# USB.net
KiCad netlist of a schematic drawn in Altium Designer
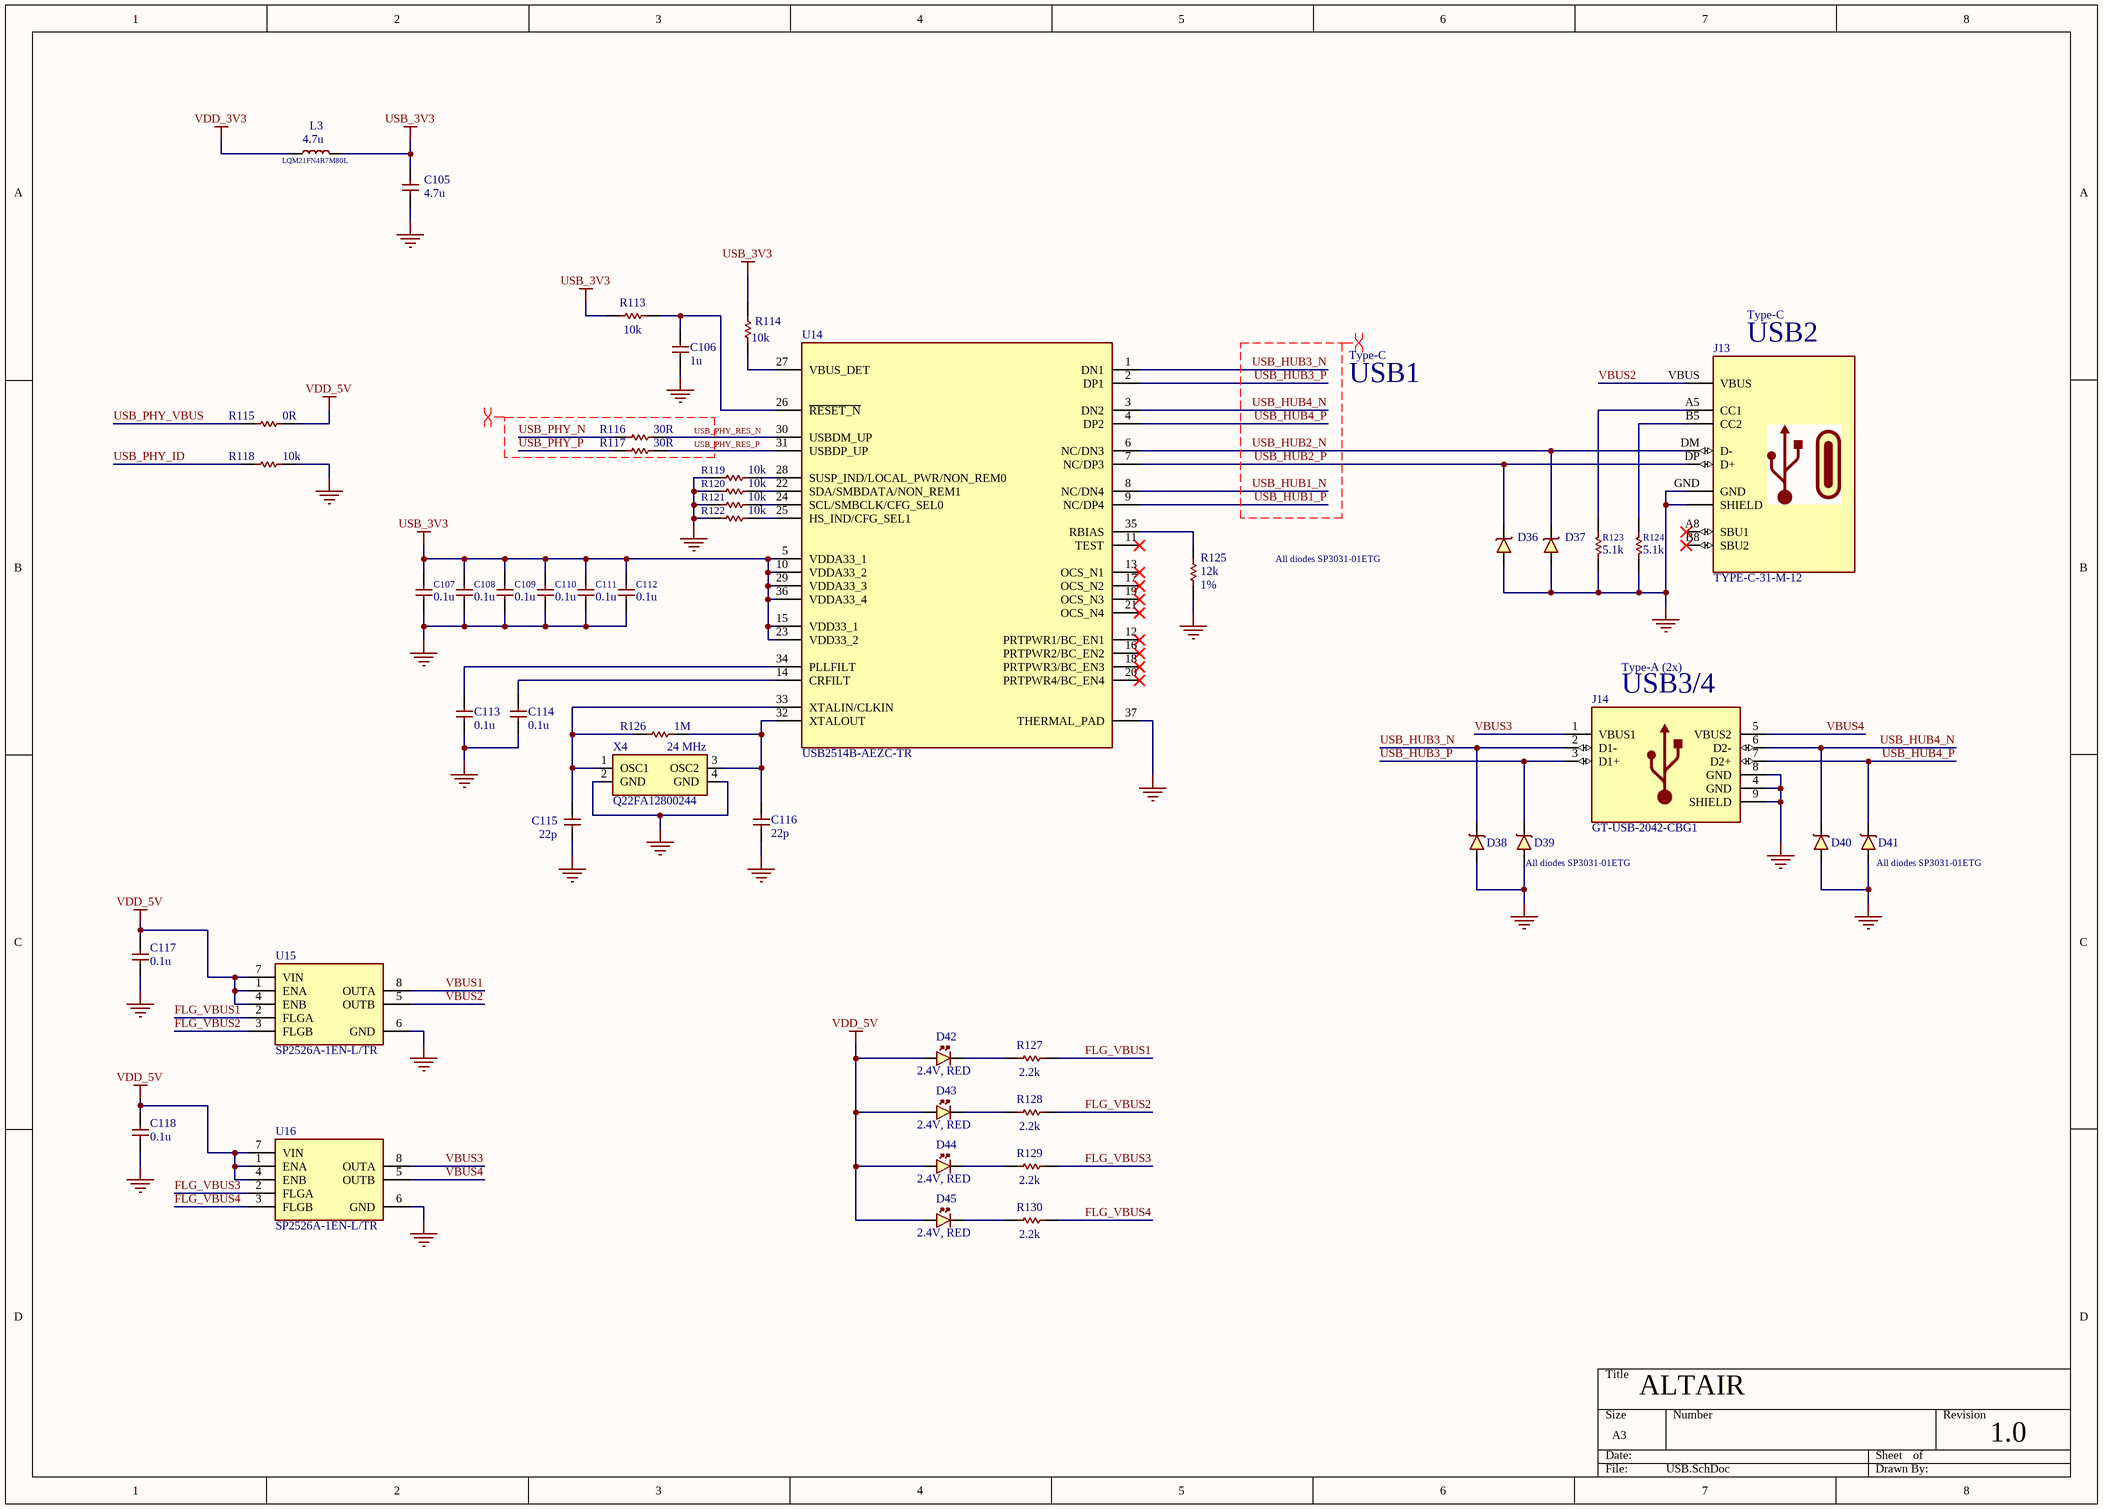
[diagram p0: USB.SchDoc]

(export (version "E")
  (design (tool "Eeschema 10.0.6"))
  (components
    (comp (ref "C105")
      (value "4.7u")
      (footprint "CAP_0402")
      (description "Capacitor SMD 0402")
      (fields (field (name "PART NO") "HGC0402R5475M250NTEJ") (field (name "JLCPCB PART #") "C22367824"))
      (libsource (lib "personalGenericLib") (part "CAP_0402"))
    )
    (comp (ref "C106")
      (value "1u")
      (footprint "CAP_0402")
      (description "Capacitor SMD 0402")
      (fields (field (name "JLCPCB PART #") "C14445") (field (name "PART NO") "CL05A105KP5NNNC"))
      (libsource (lib "personalGenericLib") (part "CAP_0402"))
    )
    (comp (ref "C107")
      (value "0.1u")
      (footprint "CAP_0402")
      (description "Capacitor SMD 0402")
      (fields (field (name "PART NO") "CL05B104KO5NNNC") (field (name "JLCPCB PART #") "C338112"))
      (libsource (lib "personalGenericLib") (part "CAP_0402"))
    )
    (comp (ref "C108")
      (value "0.1u")
      (footprint "CAP_0402")
      (description "Capacitor SMD 0402")
      (fields (field (name "PART NO") "CL05B104KO5NNNC") (field (name "JLCPCB PART #") "C338112"))
      (libsource (lib "personalGenericLib") (part "CAP_0402"))
    )
    (comp (ref "C109")
      (value "0.1u")
      (footprint "CAP_0402")
      (description "Capacitor SMD 0402")
      (fields (field (name "PART NO") "CL05B104KO5NNNC") (field (name "JLCPCB PART #") "C338112"))
      (libsource (lib "personalGenericLib") (part "CAP_0402"))
    )
    (comp (ref "C110")
      (value "0.1u")
      (footprint "CAP_0402")
      (description "Capacitor SMD 0402")
      (fields (field (name "PART NO") "CL05B104KO5NNNC") (field (name "JLCPCB PART #") "C338112"))
      (libsource (lib "personalGenericLib") (part "CAP_0402"))
    )
    (comp (ref "C111")
      (value "0.1u")
      (footprint "CAP_0402")
      (description "Capacitor SMD 0402")
      (fields (field (name "PART NO") "CL05B104KO5NNNC") (field (name "JLCPCB PART #") "C338112"))
      (libsource (lib "personalGenericLib") (part "CAP_0402"))
    )
    (comp (ref "C112")
      (value "0.1u")
      (footprint "CAP_0402")
      (description "Capacitor SMD 0402")
      (fields (field (name "PART NO") "CL05B104KO5NNNC") (field (name "JLCPCB PART #") "C338112"))
      (libsource (lib "personalGenericLib") (part "CAP_0402"))
    )
    (comp (ref "C113")
      (value "0.1u")
      (footprint "CAP_0402")
      (description "Capacitor SMD 0402")
      (fields (field (name "PART NO") "CL05B104KO5NNNC") (field (name "JLCPCB PART #") "C338112"))
      (libsource (lib "personalGenericLib") (part "CAP_0402"))
    )
    (comp (ref "C114")
      (value "0.1u")
      (footprint "CAP_0402")
      (description "Capacitor SMD 0402")
      (fields (field (name "PART NO") "CL05B104KO5NNNC") (field (name "JLCPCB PART #") "C338112"))
      (libsource (lib "personalGenericLib") (part "CAP_0402"))
    )
    (comp (ref "C115")
      (value "22p")
      (footprint "CAP_0402")
      (description "Capacitor SMD 0402")
      (fields (field (name "PART NO") "CC0402JRNPO8BN220") (field (name "JLCPCB PART #") "C541361"))
      (libsource (lib "personalGenericLib") (part "CAP_0402"))
    )
    (comp (ref "C116")
      (value "22p")
      (footprint "CAP_0402")
      (description "Capacitor SMD 0402")
      (fields (field (name "PART NO") "CC0402JRNPO8BN220") (field (name "JLCPCB PART #") "C541361"))
      (libsource (lib "personalGenericLib") (part "CAP_0402"))
    )
    (comp (ref "C117")
      (value "0.1u")
      (footprint "CAP_0402")
      (description "Capacitor SMD 0402")
      (fields (field (name "PART NO") "CL05B104KO5NNNC") (field (name "JLCPCB PART #") "C338112"))
      (libsource (lib "personalGenericLib") (part "CAP_0402"))
    )
    (comp (ref "C118")
      (value "0.1u")
      (footprint "CAP_0402")
      (description "Capacitor SMD 0402")
      (fields (field (name "PART NO") "CL05B104KO5NNNC") (field (name "JLCPCB PART #") "C338112"))
      (libsource (lib "personalGenericLib") (part "CAP_0402"))
    )
    (comp (ref "D36")
      (value "SP3031-01ETG")
      (footprint "SP303101ETG")
      (description "TVS Diode (Uni-directional)")
      (fields (field (name "JLCPCB PART #") "C207283"))
      (libsource (lib "personalGenericLib") (part "SP3031-01ETG"))
    )
    (comp (ref "D37")
      (value "SP3031-01ETG")
      (footprint "SP303101ETG")
      (description "TVS Diode (Uni-directional)")
      (fields (field (name "JLCPCB PART #") "C207283"))
      (libsource (lib "personalGenericLib") (part "SP3031-01ETG"))
    )
    (comp (ref "D38")
      (value "SP3031-01ETG")
      (footprint "SP303101ETG")
      (description "TVS Diode (Uni-directional)")
      (fields (field (name "JLCPCB PART #") "C207283"))
      (libsource (lib "personalGenericLib") (part "SP3031-01ETG"))
    )
    (comp (ref "D39")
      (value "SP3031-01ETG")
      (footprint "SP303101ETG")
      (description "TVS Diode (Uni-directional)")
      (fields (field (name "JLCPCB PART #") "C207283"))
      (libsource (lib "personalGenericLib") (part "SP3031-01ETG"))
    )
    (comp (ref "D40")
      (value "SP3031-01ETG")
      (footprint "SP303101ETG")
      (description "TVS Diode (Uni-directional)")
      (fields (field (name "JLCPCB PART #") "C207283"))
      (libsource (lib "personalGenericLib") (part "SP3031-01ETG"))
    )
    (comp (ref "D41")
      (value "SP3031-01ETG")
      (footprint "SP303101ETG")
      (description "TVS Diode (Uni-directional)")
      (fields (field (name "JLCPCB PART #") "C207283"))
      (libsource (lib "personalGenericLib") (part "SP3031-01ETG"))
    )
    (comp (ref "D42")
      (value "RED")
      (footprint "LED_0805_RED")
      (description "LED 0805 RED SMD")
      (fields
        (field (name "JLCPCB PART #") "C497952")
        (field (name "NOTE/MISC") "2.4V, RED")
        (field (name "PART NO") "HL-PSC-2012S9AC")
      )
      (libsource (lib "personalGenericLib") (part "LED_0805_RED"))
    )
    (comp (ref "D43")
      (value "RED")
      (footprint "LED_0805_RED")
      (description "LED 0805 RED SMD")
      (fields
        (field (name "JLCPCB PART #") "C497952")
        (field (name "NOTE/MISC") "2.4V, RED")
        (field (name "PART NO") "HL-PSC-2012S9AC")
      )
      (libsource (lib "personalGenericLib") (part "LED_0805_RED"))
    )
    (comp (ref "D44")
      (value "RED")
      (footprint "LED_0805_RED")
      (description "LED 0805 RED SMD")
      (fields
        (field (name "JLCPCB PART #") "C497952")
        (field (name "NOTE/MISC") "2.4V, RED")
        (field (name "PART NO") "HL-PSC-2012S9AC")
      )
      (libsource (lib "personalGenericLib") (part "LED_0805_RED"))
    )
    (comp (ref "D45")
      (value "RED")
      (footprint "LED_0805_RED")
      (description "LED 0805 RED SMD")
      (fields
        (field (name "JLCPCB PART #") "C497952")
        (field (name "NOTE/MISC") "2.4V, RED")
        (field (name "PART NO") "HL-PSC-2012S9AC")
      )
      (libsource (lib "personalGenericLib") (part "LED_0805_RED"))
    )
    (comp (ref "J13")
      (value "TYPE-C-31-M-12")
      (footprint "HRO_TYPE-C-31-M-12")
      (description "USB2.0, Type C, Top mount, CH 1.68mm, Dual Row SMT")
      (fields (field (name "JLCPCB PART #") "C165948"))
      (libsource (lib "personalGenericLib") (part "TYPE-C-31-M-12"))
    )
    (comp (ref "J14")
      (value "GT-USB-2042-CBG1")
      (footprint "GT-USB-2042-CBG1")
      (description "2x USB Type-A Female Connector")
      (fields (field (name "JLCPCB PART #") "C2911522"))
      (libsource (lib "personalGenericLib") (part "GT-USB-2042-CBG1"))
    )
    (comp (ref "L3")
      (value "4.7u")
      (footprint "INDC2012X145N")
      (description "Inductor")
      (fields
        (field (name "NOTE/MISC") "LQM21FN4R7M80L")
        (field (name "PART NO") "LQM21FN4R7M80L")
        (field (name "JLCPCB PART #") "C464406")
      )
      (libsource (lib "personalGenericLib") (part "LQM21FN4R7M70L"))
    )
    (comp (ref "R113")
      (value "10k")
      (footprint "RES_0402")
      (description "Resistor SMD 0402")
      (fields (field (name "JLCPCB PART #") "C60489") (field (name "PART NO") "RC0402JR-0710KL"))
      (libsource (lib "personalGenericLib") (part "RES_0402"))
    )
    (comp (ref "R114")
      (value "10k")
      (footprint "RES_0402")
      (description "Resistor SMD 0402")
      (fields (field (name "JLCPCB PART #") "C60489") (field (name "PART NO") "RC0402JR-0710KL"))
      (libsource (lib "personalGenericLib") (part "RES_0402"))
    )
    (comp (ref "R115")
      (value "0R")
      (footprint "RES_0402")
      (description "Resistor SMD 0402")
      (fields (field (name "JLCPCB PART #") "C60485") (field (name "PART NO") "RC0402JR-070RL"))
      (libsource (lib "personalGenericLib") (part "RES_0402"))
    )
    (comp (ref "R116")
      (value "30R")
      (footprint "RES_0402")
      (description "Resistor SMD 0402")
      (fields (field (name "JLCPCB PART #") "C138007") (field (name "PART NO") "RC0402FR-0730RL"))
      (libsource (lib "personalGenericLib") (part "RES_0402"))
    )
    (comp (ref "R117")
      (value "30R")
      (footprint "RES_0402")
      (description "Resistor SMD 0402")
      (fields (field (name "JLCPCB PART #") "C138007") (field (name "PART NO") "RC0402FR-0730RL"))
      (libsource (lib "personalGenericLib") (part "RES_0402"))
    )
    (comp (ref "R118")
      (value "10k")
      (footprint "RES_0402")
      (description "Resistor SMD 0402")
      (fields (field (name "JLCPCB PART #") "C60489") (field (name "PART NO") "RC0402JR-0710KL"))
      (libsource (lib "personalGenericLib") (part "RES_0402"))
    )
    (comp (ref "R119")
      (value "10k")
      (footprint "RES_0402")
      (description "Resistor SMD 0402")
      (fields (field (name "JLCPCB PART #") "C60489") (field (name "PART NO") "RC0402JR-0710KL"))
      (libsource (lib "personalGenericLib") (part "RES_0402"))
    )
    (comp (ref "R120")
      (value "10k")
      (footprint "RES_0402")
      (description "Resistor SMD 0402")
      (fields (field (name "JLCPCB PART #") "C60489") (field (name "PART NO") "RC0402JR-0710KL"))
      (libsource (lib "personalGenericLib") (part "RES_0402"))
    )
    (comp (ref "R121")
      (value "10k")
      (footprint "RES_0402")
      (description "Resistor SMD 0402")
      (fields (field (name "JLCPCB PART #") "C60489") (field (name "PART NO") "RC0402JR-0710KL"))
      (libsource (lib "personalGenericLib") (part "RES_0402"))
    )
    (comp (ref "R122")
      (value "10k")
      (footprint "RES_0402")
      (description "Resistor SMD 0402")
      (fields (field (name "JLCPCB PART #") "C60489") (field (name "PART NO") "RC0402JR-0710KL"))
      (libsource (lib "personalGenericLib") (part "RES_0402"))
    )
    (comp (ref "R123")
      (value "5.1k")
      (footprint "RES_0402")
      (description "Resistor SMD 0402")
      (fields (field (name "JLCPCB PART #") "C105873") (field (name "PART NO") "RC0402JR-075K1L"))
      (libsource (lib "personalGenericLib") (part "RES_0402"))
    )
    (comp (ref "R124")
      (value "5.1k")
      (footprint "RES_0402")
      (description "Resistor SMD 0402")
      (fields (field (name "JLCPCB PART #") "C105873") (field (name "PART NO") "RC0402JR-075K1L"))
      (libsource (lib "personalGenericLib") (part "RES_0402"))
    )
    (comp (ref "R125")
      (value "12k")
      (footprint "RES_0402")
      (description "Resistor SMD 0402")
      (fields
        (field (name "JLCPCB PART #") "C114760")
        (field (name "NOTE/MISC") "1%")
        (field (name "PART NO") "RC0402FR-0712KL")
      )
      (libsource (lib "personalGenericLib") (part "RES_0402"))
    )
    (comp (ref "R126")
      (value "1M")
      (footprint "RES_0402")
      (description "Resistor SMD 0402")
      (fields (field (name "JLCPCB PART #") "C93949") (field (name "PART NO") "RC0402JR-071ML"))
      (libsource (lib "personalGenericLib") (part "RES_0402"))
    )
    (comp (ref "R127")
      (value "2.2k")
      (footprint "RES_0402")
      (description "Resistor SMD 0402")
      (fields (field (name "JLCPCB PART #") "C163447") (field (name "PART NO") "RC0402JR-072K2L"))
      (libsource (lib "personalGenericLib") (part "RES_0402"))
    )
    (comp (ref "R128")
      (value "2.2k")
      (footprint "RES_0402")
      (description "Resistor SMD 0402")
      (fields (field (name "JLCPCB PART #") "C163447") (field (name "PART NO") "RC0402JR-072K2L"))
      (libsource (lib "personalGenericLib") (part "RES_0402"))
    )
    (comp (ref "R129")
      (value "2.2k")
      (footprint "RES_0402")
      (description "Resistor SMD 0402")
      (fields (field (name "JLCPCB PART #") "C163447") (field (name "PART NO") "RC0402JR-072K2L"))
      (libsource (lib "personalGenericLib") (part "RES_0402"))
    )
    (comp (ref "R130")
      (value "2.2k")
      (footprint "RES_0402")
      (description "Resistor SMD 0402")
      (fields (field (name "JLCPCB PART #") "C163447") (field (name "PART NO") "RC0402JR-072K2L"))
      (libsource (lib "personalGenericLib") (part "RES_0402"))
    )
    (comp (ref "U14")
      (value "USB2514B-AEZC-TR")
      (footprint "QFN50P600X600X100-37N-D")
      (description "USB Hub")
      (fields (field (name "JLCPCB PART #") "C16251"))
      (libsource (lib "personalGenericLib") (part "USB2514B-AEZC-TR"))
    )
    (comp (ref "U15")
      (value "SP2526A-1EN-L/TR")
      (footprint "SOIC127P600X175-8N")
      (fields (field (name "JLCPCB PART #") "C37347"))
      (libsource (lib "personalGenericLib") (part "SP2526A-1EN-L/TR"))
    )
    (comp (ref "U16")
      (value "SP2526A-1EN-L/TR")
      (footprint "SOIC127P600X175-8N")
      (fields (field (name "JLCPCB PART #") "C37347"))
      (libsource (lib "personalGenericLib") (part "SP2526A-1EN-L/TR"))
    )
    (comp (ref "X4")
      (value "Q22FA12800244")
      (footprint "Q22FA12800244")
      (description "24 MHz Crystal SMD 4-Pin 2.0x1.6mm 4 Pins Alt")
      (fields
        (field (name "JLCPCB PART #") "C255880")
        (field (name "NOTE/MISC") "24 MHz")
        (field (name "PART NO") "Q22FA12800244")
      )
      (libsource (lib "personalGenericLib") (part "Q22FA12800244"))
    )
  )
  (nets
    (net (code "1") (name "/FLG_VBUS1") (class "Default")
      (node (ref "R127") (pin "2") (pinfunction "2_2") (pintype "passive"))
      (node (ref "U15") (pin "2") (pinfunction "FLGA_2") (pintype "passive"))
    )
    (net (code "2") (name "/FLG_VBUS2") (class "Default")
      (node (ref "R128") (pin "2") (pinfunction "2_2") (pintype "passive"))
      (node (ref "U15") (pin "3") (pinfunction "FLGB_3") (pintype "passive"))
    )
    (net (code "3") (name "/FLG_VBUS3") (class "Default")
      (node (ref "R129") (pin "2") (pinfunction "2_2") (pintype "passive"))
      (node (ref "U16") (pin "2") (pinfunction "FLGA_2") (pintype "passive"))
    )
    (net (code "4") (name "/FLG_VBUS4") (class "Default")
      (node (ref "R130") (pin "2") (pinfunction "2_2") (pintype "passive"))
      (node (ref "U16") (pin "3") (pinfunction "FLGB_3") (pintype "passive"))
    )
    (net (code "5") (name "/USB_HUB1_N") (class "Default")
      (node (ref "U14") (pin "8") (pinfunction "NC/DN4_8") (pintype "passive"))
    )
    (net (code "6") (name "/USB_HUB1_P") (class "Default")
      (node (ref "U14") (pin "9") (pinfunction "NC/DP4_9") (pintype "passive"))
    )
    (net (code "7") (name "/USB_HUB2_N") (class "Default")
      (node (ref "D37") (pin "1") (pinfunction "K_1") (pintype "passive"))
      (node (ref "J13") (pin "DM") (pinfunction "D-_DM") (pintype "bidirectional"))
      (node (ref "U14") (pin "6") (pinfunction "NC/DN3_6") (pintype "passive"))
    )
    (net (code "8") (name "/USB_HUB2_P") (class "Default")
      (node (ref "D36") (pin "1") (pinfunction "K_1") (pintype "passive"))
      (node (ref "J13") (pin "DP") (pinfunction "D+_DP") (pintype "bidirectional"))
      (node (ref "U14") (pin "7") (pinfunction "NC/DP3_7") (pintype "passive"))
    )
    (net (code "9") (name "/USB_HUB3_N") (class "Default")
      (node (ref "D38") (pin "1") (pinfunction "K_1") (pintype "passive"))
      (node (ref "J14") (pin "2") (pinfunction "D1-_2") (pintype "bidirectional"))
      (node (ref "U14") (pin "1") (pinfunction "DN1_1") (pintype "passive"))
    )
    (net (code "10") (name "/USB_HUB3_P") (class "Default")
      (node (ref "D39") (pin "1") (pinfunction "K_1") (pintype "passive"))
      (node (ref "J14") (pin "3") (pinfunction "D1+_3") (pintype "bidirectional"))
      (node (ref "U14") (pin "2") (pinfunction "DP1_2") (pintype "passive"))
    )
    (net (code "11") (name "/USB_HUB4_N") (class "Default")
      (node (ref "D40") (pin "1") (pinfunction "K_1") (pintype "passive"))
      (node (ref "J14") (pin "6") (pinfunction "D2-_6") (pintype "bidirectional"))
      (node (ref "U14") (pin "3") (pinfunction "DN2_3") (pintype "passive"))
    )
    (net (code "12") (name "/USB_HUB4_P") (class "Default")
      (node (ref "D41") (pin "1") (pinfunction "K_1") (pintype "passive"))
      (node (ref "J14") (pin "7") (pinfunction "D2+_7") (pintype "bidirectional"))
      (node (ref "U14") (pin "4") (pinfunction "DP2_4") (pintype "passive"))
    )
    (net (code "13") (name "/USB_PHY_ID") (class "Default")
      (node (ref "R118") (pin "1") (pinfunction "1_1") (pintype "passive"))
    )
    (net (code "14") (name "/USB_PHY_N") (class "Default")
      (node (ref "R116") (pin "1") (pinfunction "1_1") (pintype "passive"))
    )
    (net (code "15") (name "/USB_PHY_P") (class "Default")
      (node (ref "R117") (pin "1") (pinfunction "1_1") (pintype "passive"))
    )
    (net (code "16") (name "/USB_PHY_RES_N") (class "Default")
      (node (ref "R116") (pin "2") (pinfunction "2_2") (pintype "passive"))
      (node (ref "U14") (pin "30") (pinfunction "USBDM_UP_30") (pintype "passive"))
    )
    (net (code "17") (name "/USB_PHY_RES_P") (class "Default")
      (node (ref "R117") (pin "2") (pinfunction "2_2") (pintype "passive"))
      (node (ref "U14") (pin "31") (pinfunction "USBDP_UP_31") (pintype "passive"))
    )
    (net (code "18") (name "/USB_PHY_VBUS") (class "Default")
      (node (ref "R115") (pin "1") (pinfunction "1_1") (pintype "passive"))
    )
    (net (code "19") (name "/VBUS1") (class "Default")
      (node (ref "U15") (pin "8") (pinfunction "OUTA_8") (pintype "passive"))
    )
    (net (code "20") (name "/VBUS2") (class "Default")
      (node (ref "J13") (pin "VBUS") (pinfunction "VBUS_VBUS") (pintype "passive"))
      (node (ref "U15") (pin "5") (pinfunction "OUTB_5") (pintype "passive"))
    )
    (net (code "21") (name "/VBUS3") (class "Default")
      (node (ref "J14") (pin "1") (pinfunction "VBUS1_1") (pintype "passive"))
      (node (ref "U16") (pin "8") (pinfunction "OUTA_8") (pintype "passive"))
    )
    (net (code "22") (name "/VBUS4") (class "Default")
      (node (ref "J14") (pin "5") (pinfunction "VBUS2_5") (pintype "passive"))
      (node (ref "U16") (pin "5") (pinfunction "OUTB_5") (pintype "passive"))
    )
    (net (code "23") (name "GND") (class "Default")
      (node (ref "C105") (pin "1") (pinfunction "1_1") (pintype "passive"))
      (node (ref "C106") (pin "1") (pinfunction "1_1") (pintype "passive"))
      (node (ref "C107") (pin "1") (pinfunction "1_1") (pintype "passive"))
      (node (ref "C108") (pin "1") (pinfunction "1_1") (pintype "passive"))
      (node (ref "C109") (pin "1") (pinfunction "1_1") (pintype "passive"))
      (node (ref "C110") (pin "1") (pinfunction "1_1") (pintype "passive"))
      (node (ref "C111") (pin "1") (pinfunction "1_1") (pintype "passive"))
      (node (ref "C112") (pin "1") (pinfunction "1_1") (pintype "passive"))
      (node (ref "C113") (pin "1") (pinfunction "1_1") (pintype "passive"))
      (node (ref "C114") (pin "1") (pinfunction "1_1") (pintype "passive"))
      (node (ref "C115") (pin "1") (pinfunction "1_1") (pintype "passive"))
      (node (ref "C116") (pin "1") (pinfunction "1_1") (pintype "passive"))
      (node (ref "C117") (pin "1") (pinfunction "1_1") (pintype "passive"))
      (node (ref "C118") (pin "1") (pinfunction "1_1") (pintype "passive"))
      (node (ref "D36") (pin "2") (pinfunction "A_2") (pintype "passive"))
      (node (ref "D37") (pin "2") (pinfunction "A_2") (pintype "passive"))
      (node (ref "D38") (pin "2") (pinfunction "A_2") (pintype "passive"))
      (node (ref "D39") (pin "2") (pinfunction "A_2") (pintype "passive"))
      (node (ref "D40") (pin "2") (pinfunction "A_2") (pintype "passive"))
      (node (ref "D41") (pin "2") (pinfunction "A_2") (pintype "passive"))
      (node (ref "J13") (pin "GND") (pinfunction "GND_GND") (pintype "passive"))
      (node (ref "J13") (pin "SHLD") (pinfunction "SHIELD_SHLD") (pintype "passive"))
      (node (ref "J14") (pin "4") (pinfunction "GND_4") (pintype "passive"))
      (node (ref "J14") (pin "8") (pinfunction "GND_8") (pintype "passive"))
      (node (ref "J14") (pin "9") (pinfunction "SHIELD_9") (pintype "passive"))
      (node (ref "R118") (pin "2") (pinfunction "2_2") (pintype "passive"))
      (node (ref "R119") (pin "1") (pinfunction "1_1") (pintype "passive"))
      (node (ref "R120") (pin "1") (pinfunction "1_1") (pintype "passive"))
      (node (ref "R121") (pin "1") (pinfunction "1_1") (pintype "passive"))
      (node (ref "R122") (pin "1") (pinfunction "1_1") (pintype "passive"))
      (node (ref "R123") (pin "2") (pinfunction "2_2") (pintype "passive"))
      (node (ref "R124") (pin "2") (pinfunction "2_2") (pintype "passive"))
      (node (ref "R125") (pin "1") (pinfunction "1_1") (pintype "passive"))
      (node (ref "U14") (pin "37") (pinfunction "THERMAL_PAD_37") (pintype "passive"))
      (node (ref "U15") (pin "6") (pinfunction "GND_6") (pintype "passive"))
      (node (ref "U16") (pin "6") (pinfunction "GND_6") (pintype "passive"))
      (node (ref "X4") (pin "2") (pinfunction "GND_2") (pintype "passive"))
      (node (ref "X4") (pin "4") (pinfunction "GND_4") (pintype "passive"))
    )
    (net (code "24") (name "Net-(D42-PadK)") (class "Default")
      (node (ref "D42") (pin "K") (pinfunction "K_K") (pintype "passive"))
      (node (ref "R127") (pin "1") (pinfunction "1_1") (pintype "passive"))
    )
    (net (code "25") (name "Net-(D43-PadK)") (class "Default")
      (node (ref "D43") (pin "K") (pinfunction "K_K") (pintype "passive"))
      (node (ref "R128") (pin "1") (pinfunction "1_1") (pintype "passive"))
    )
    (net (code "26") (name "Net-(D44-PadK)") (class "Default")
      (node (ref "D44") (pin "K") (pinfunction "K_K") (pintype "passive"))
      (node (ref "R129") (pin "1") (pinfunction "1_1") (pintype "passive"))
    )
    (net (code "27") (name "Net-(D45-PadK)") (class "Default")
      (node (ref "D45") (pin "K") (pinfunction "K_K") (pintype "passive"))
      (node (ref "R130") (pin "1") (pinfunction "1_1") (pintype "passive"))
    )
    (net (code "28") (name "Net-(J13-CC1)") (class "Default")
      (node (ref "J13") (pin "A5") (pinfunction "CC1_A5") (pintype "passive"))
      (node (ref "R123") (pin "1") (pinfunction "1_1") (pintype "passive"))
    )
    (net (code "29") (name "Net-(J13-CC2)") (class "Default")
      (node (ref "J13") (pin "B5") (pinfunction "CC2_B5") (pintype "passive"))
      (node (ref "R124") (pin "1") (pinfunction "1_1") (pintype "passive"))
    )
    (net (code "30") (name "Net-(U14-CRFILT)") (class "Default")
      (node (ref "C114") (pin "2") (pinfunction "2_2") (pintype "passive"))
      (node (ref "U14") (pin "14") (pinfunction "CRFILT_14") (pintype "passive"))
    )
    (net (code "31") (name "Net-(U14-HS_IND{slash}CFG_SEL1)") (class "Default")
      (node (ref "R122") (pin "2") (pinfunction "2_2") (pintype "passive"))
      (node (ref "U14") (pin "25") (pinfunction "HS_IND/CFG_SEL1_25") (pintype "passive"))
    )
    (net (code "32") (name "Net-(U14-PLLFILT)") (class "Default")
      (node (ref "C113") (pin "2") (pinfunction "2_2") (pintype "passive"))
      (node (ref "U14") (pin "34") (pinfunction "PLLFILT_34") (pintype "passive"))
    )
    (net (code "33") (name "Net-(U14-RBIAS)") (class "Default")
      (node (ref "R125") (pin "2") (pinfunction "2_2") (pintype "passive"))
      (node (ref "U14") (pin "35") (pinfunction "RBIAS_35") (pintype "passive"))
    )
    (net (code "34") (name "Net-(U14-SCL{slash}SMBCLK{slash}CFG_SEL0)") (class "Default")
      (node (ref "R121") (pin "2") (pinfunction "2_2") (pintype "passive"))
      (node (ref "U14") (pin "24") (pinfunction "SCL/SMBCLK/CFG_SEL0_24") (pintype "passive"))
    )
    (net (code "35") (name "Net-(U14-SDA{slash}SMBDATA{slash}NON_REM1)") (class "Default")
      (node (ref "R120") (pin "2") (pinfunction "2_2") (pintype "passive"))
      (node (ref "U14") (pin "22") (pinfunction "SDA/SMBDATA/NON_REM1_22") (pintype "passive"))
    )
    (net (code "36") (name "Net-(U14-SUSP_IND{slash}LOCAL_PWR{slash}NON_REM0)") (class "Default")
      (node (ref "R119") (pin "2") (pinfunction "2_2") (pintype "passive"))
      (node (ref "U14") (pin "28") (pinfunction "SUSP_IND/LOCAL_PWR/NON_REM0_28") (pintype "passive"))
    )
    (net (code "37") (name "Net-(U14-VBUS_DET)") (class "Default")
      (node (ref "R114") (pin "2") (pinfunction "2_2") (pintype "passive"))
      (node (ref "U14") (pin "27") (pinfunction "VBUS_DET_27") (pintype "passive"))
    )
    (net (code "38") (name "Net-(U14-XTALIN{slash}CLKIN)") (class "Default")
      (node (ref "C115") (pin "2") (pinfunction "2_2") (pintype "passive"))
      (node (ref "R126") (pin "2") (pinfunction "2_2") (pintype "passive"))
      (node (ref "U14") (pin "33") (pinfunction "XTALIN/CLKIN_33") (pintype "passive"))
      (node (ref "X4") (pin "1") (pinfunction "OSC1_1") (pintype "passive"))
    )
    (net (code "39") (name "Net-(U14-XTALOUT)") (class "Default")
      (node (ref "C116") (pin "2") (pinfunction "2_2") (pintype "passive"))
      (node (ref "R126") (pin "1") (pinfunction "1_1") (pintype "passive"))
      (node (ref "U14") (pin "32") (pinfunction "XTALOUT_32") (pintype "passive"))
      (node (ref "X4") (pin "3") (pinfunction "OSC2_3") (pintype "passive"))
    )
    (net (code "40") (name "Net-(U14-~{RESET_N})") (class "Default")
      (node (ref "C106") (pin "2") (pinfunction "2_2") (pintype "passive"))
      (node (ref "R113") (pin "2") (pinfunction "2_2") (pintype "passive"))
      (node (ref "U14") (pin "26") (pinfunction "~{RESET_N}_26") (pintype "passive"))
    )
    (net (code "41") (name "USB_3V3") (class "Default")
      (node (ref "C105") (pin "2") (pinfunction "2_2") (pintype "passive"))
      (node (ref "C107") (pin "2") (pinfunction "2_2") (pintype "passive"))
      (node (ref "C108") (pin "2") (pinfunction "2_2") (pintype "passive"))
      (node (ref "C109") (pin "2") (pinfunction "2_2") (pintype "passive"))
      (node (ref "C110") (pin "2") (pinfunction "2_2") (pintype "passive"))
      (node (ref "C111") (pin "2") (pinfunction "2_2") (pintype "passive"))
      (node (ref "C112") (pin "2") (pinfunction "2_2") (pintype "passive"))
      (node (ref "L3") (pin "2") (pinfunction "2_2") (pintype "passive"))
      (node (ref "R113") (pin "1") (pinfunction "1_1") (pintype "passive"))
      (node (ref "R114") (pin "1") (pinfunction "1_1") (pintype "passive"))
      (node (ref "U14") (pin "10") (pinfunction "VDDA33_2_10") (pintype "passive"))
      (node (ref "U14") (pin "15") (pinfunction "VDD33_1_15") (pintype "passive"))
      (node (ref "U14") (pin "23") (pinfunction "VDD33_2_23") (pintype "passive"))
      (node (ref "U14") (pin "29") (pinfunction "VDDA33_3_29") (pintype "passive"))
      (node (ref "U14") (pin "36") (pinfunction "VDDA33_4_36") (pintype "passive"))
      (node (ref "U14") (pin "5") (pinfunction "VDDA33_1_5") (pintype "passive"))
    )
    (net (code "42") (name "VDD_3V3") (class "Default")
      (node (ref "L3") (pin "1") (pinfunction "1_1") (pintype "passive"))
    )
    (net (code "43") (name "VDD_5V") (class "Default")
      (node (ref "C117") (pin "2") (pinfunction "2_2") (pintype "passive"))
      (node (ref "C118") (pin "2") (pinfunction "2_2") (pintype "passive"))
      (node (ref "D42") (pin "A") (pinfunction "A_A") (pintype "passive"))
      (node (ref "D43") (pin "A") (pinfunction "A_A") (pintype "passive"))
      (node (ref "D44") (pin "A") (pinfunction "A_A") (pintype "passive"))
      (node (ref "D45") (pin "A") (pinfunction "A_A") (pintype "passive"))
      (node (ref "R115") (pin "2") (pinfunction "2_2") (pintype "passive"))
      (node (ref "U15") (pin "1") (pinfunction "ENA_1") (pintype "passive"))
      (node (ref "U15") (pin "4") (pinfunction "ENB_4") (pintype "passive"))
      (node (ref "U15") (pin "7") (pinfunction "VIN_7") (pintype "power_in"))
      (node (ref "U16") (pin "1") (pinfunction "ENA_1") (pintype "passive"))
      (node (ref "U16") (pin "4") (pinfunction "ENB_4") (pintype "passive"))
      (node (ref "U16") (pin "7") (pinfunction "VIN_7") (pintype "power_in"))
    )
    (net (code "44") (name "unconnected-(J13-SBU1-PadA8)") (class "Default")
      (node (ref "J13") (pin "A8") (pinfunction "SBU1_A8") (pintype "bidirectional+no_connect"))
    )
    (net (code "45") (name "unconnected-(J13-SBU2-PadB8)") (class "Default")
      (node (ref "J13") (pin "B8") (pinfunction "SBU2_B8") (pintype "bidirectional+no_connect"))
    )
    (net (code "46") (name "unconnected-(U14-OCS_N1-Pad13)") (class "Default")
      (node (ref "U14") (pin "13") (pinfunction "OCS_N1_13") (pintype "passive+no_connect"))
    )
    (net (code "47") (name "unconnected-(U14-OCS_N2-Pad17)") (class "Default")
      (node (ref "U14") (pin "17") (pinfunction "OCS_N2_17") (pintype "passive+no_connect"))
    )
    (net (code "48") (name "unconnected-(U14-OCS_N3-Pad19)") (class "Default")
      (node (ref "U14") (pin "19") (pinfunction "OCS_N3_19") (pintype "passive+no_connect"))
    )
    (net (code "49") (name "unconnected-(U14-OCS_N4-Pad21)") (class "Default")
      (node (ref "U14") (pin "21") (pinfunction "OCS_N4_21") (pintype "passive+no_connect"))
    )
    (net (code "50") (name "unconnected-(U14-PRTPWR1{slash}BC_EN1-Pad12)") (class "Default")
      (node (ref "U14") (pin "12") (pinfunction "PRTPWR1/BC_EN1_12") (pintype "passive+no_connect"))
    )
    (net (code "51") (name "unconnected-(U14-PRTPWR2{slash}BC_EN2-Pad16)") (class "Default")
      (node (ref "U14") (pin "16") (pinfunction "PRTPWR2/BC_EN2_16") (pintype "passive+no_connect"))
    )
    (net (code "52") (name "unconnected-(U14-PRTPWR3{slash}BC_EN3-Pad18)") (class "Default")
      (node (ref "U14") (pin "18") (pinfunction "PRTPWR3/BC_EN3_18") (pintype "passive+no_connect"))
    )
    (net (code "53") (name "unconnected-(U14-PRTPWR4{slash}BC_EN4-Pad20)") (class "Default")
      (node (ref "U14") (pin "20") (pinfunction "PRTPWR4/BC_EN4_20") (pintype "passive+no_connect"))
    )
    (net (code "54") (name "unconnected-(U14-TEST-Pad11)") (class "Default")
      (node (ref "U14") (pin "11") (pinfunction "TEST_11") (pintype "passive+no_connect"))
    )
  )
)
